# 1.net
KiCad netlist of a schematic drawn in EAGLE
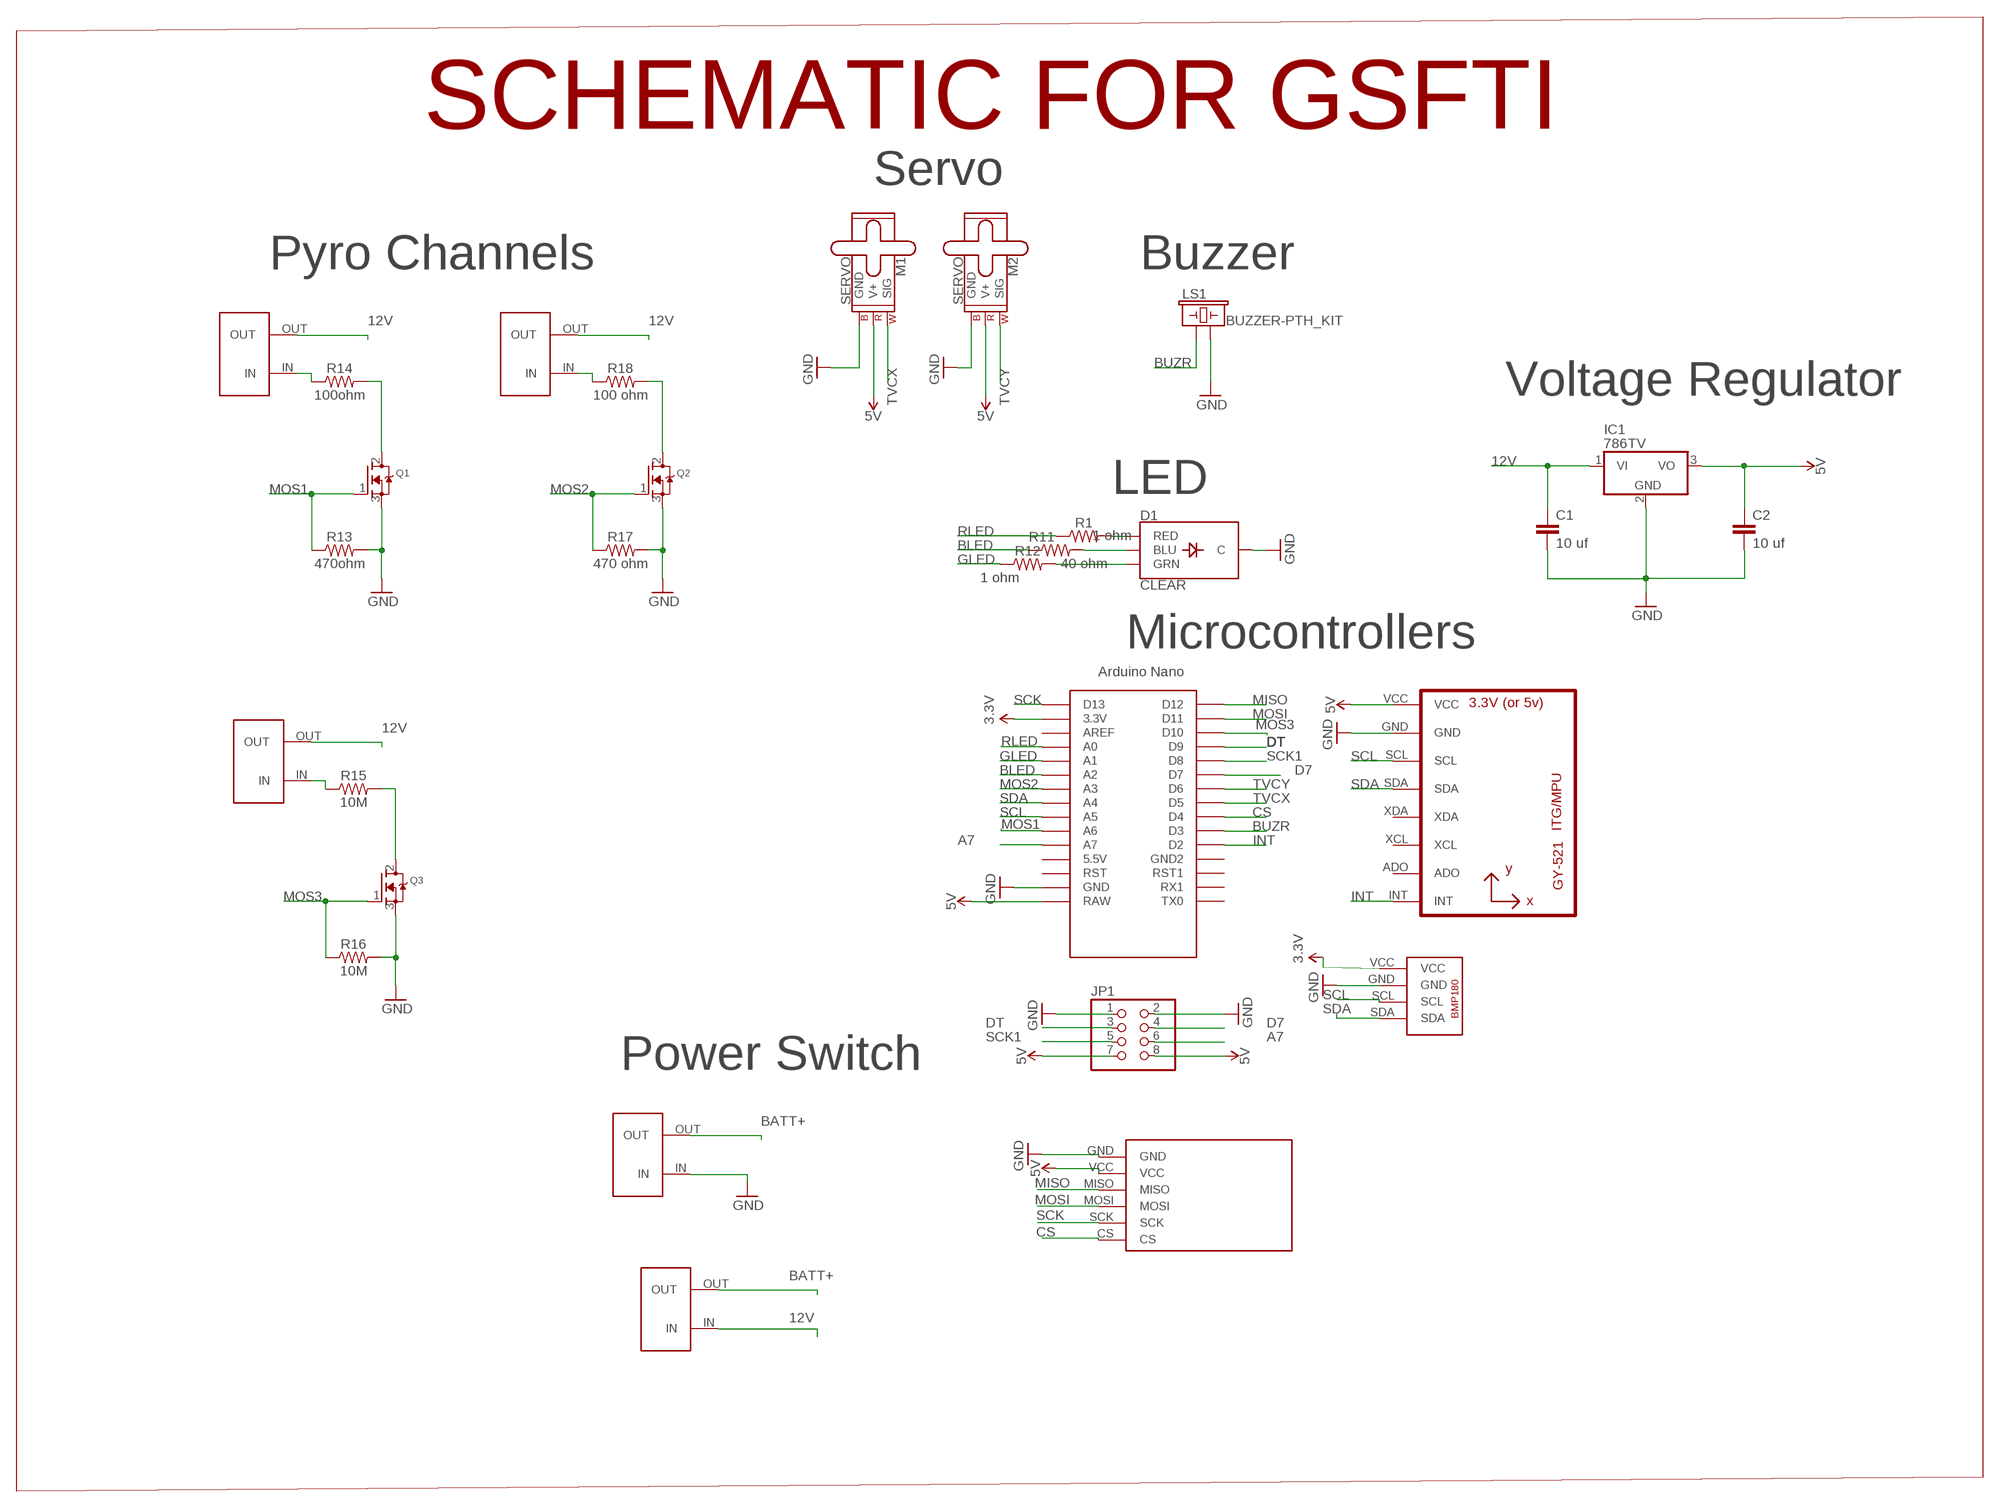
[diagram p0: schematic, sheet 1]

(export (version "E")
  (design (tool "Eeschema 10.0.6"))
  (components
    (comp (ref "C1")
      (value "10 uf")
      (footprint "eagle-import:C2.5-3")
      (libsource (lib "eagle-import") (part "C2,5-3"))
    )
    (comp (ref "C2")
      (value "10 uf")
      (footprint "eagle-import:C2.5-3")
      (libsource (lib "eagle-import") (part "C2,5-3"))
    )
    (comp (ref "D1")
      (value "CLEAR")
      (footprint "eagle-import:LED-RGB-THRU")
      (libsource (lib "eagle-import") (part "LED-RGB-CCCLEAR"))
    )
    (comp (ref "IC1")
      (value "786TV")
      (footprint "eagle-import:TO220V")
      (libsource (lib "eagle-import") (part "78TV6"))
    )
    (comp (ref "JP1")
      (value "PINHD-2X4")
      (footprint "eagle-import:2X04")
      (libsource (lib "eagle-import") (part "PINHD-2X4"))
    )
    (comp (ref "LS1")
      (value "BUZZER-PTH_KIT")
      (footprint "eagle-import:BUZZER-12MM-KIT")
      (libsource (lib "eagle-import") (part "BUZZER-PTH_KIT"))
    )
    (comp (ref "M1")
      (value "SERVO")
      (footprint "eagle-import:1X03")
      (libsource (lib "eagle-import") (part "SERVO"))
    )
    (comp (ref "M2")
      (value "SERVO")
      (footprint "eagle-import:1X03")
      (libsource (lib "eagle-import") (part "SERVO"))
    )
    (comp (ref "Q1")
      (value "MOSFET-NGDS_TO220V")
      (footprint "eagle-import:TO220V")
      (libsource (lib "eagle-import") (part "MOSFET-NGDS_TO220V"))
    )
    (comp (ref "Q2")
      (value "MOSFET-NGDS_TO220V")
      (footprint "eagle-import:TO220V")
      (libsource (lib "eagle-import") (part "MOSFET-NGDS_TO220V"))
    )
    (comp (ref "Q3")
      (value "MOSFET-NGDS_TO220V")
      (footprint "eagle-import:TO220V")
      (libsource (lib "eagle-import") (part "MOSFET-NGDS_TO220V"))
    )
    (comp (ref "R1")
      (value "1 ohm")
      (footprint "eagle-import:AXIAL-0.3")
      (libsource (lib "eagle-import") (part "10MOHM-HORIZ-1/4W-5%"))
    )
    (comp (ref "R11")
      (value "40 ohm")
      (footprint "eagle-import:AXIAL-0.3")
      (libsource (lib "eagle-import") (part "10MOHM-HORIZ-1/4W-5%"))
    )
    (comp (ref "R12")
      (value "1 ohm")
      (footprint "eagle-import:AXIAL-0.3")
      (libsource (lib "eagle-import") (part "10MOHM-HORIZ-1/4W-5%"))
    )
    (comp (ref "R13")
      (value "470ohm")
      (footprint "eagle-import:AXIAL-0.3")
      (libsource (lib "eagle-import") (part "10MOHM-HORIZ-1/4W-5%"))
    )
    (comp (ref "R14")
      (value "100ohm")
      (footprint "eagle-import:AXIAL-0.3")
      (libsource (lib "eagle-import") (part "10MOHM-HORIZ-1/4W-5%"))
    )
    (comp (ref "R15")
      (value "10M")
      (footprint "eagle-import:AXIAL-0.3")
      (libsource (lib "eagle-import") (part "10MOHM-HORIZ-1/4W-5%"))
    )
    (comp (ref "R16")
      (value "10M")
      (footprint "eagle-import:AXIAL-0.3")
      (libsource (lib "eagle-import") (part "10MOHM-HORIZ-1/4W-5%"))
    )
    (comp (ref "R17")
      (value "470 ohm")
      (footprint "eagle-import:AXIAL-0.3")
      (libsource (lib "eagle-import") (part "10MOHM-HORIZ-1/4W-5%"))
    )
    (comp (ref "R18")
      (value "100 ohm")
      (footprint "eagle-import:AXIAL-0.3")
      (libsource (lib "eagle-import") (part "10MOHM-HORIZ-1/4W-5%"))
    )
    (comp (ref "U$1")
      (value "NANO")
      (footprint "eagle-import:NANO")
      (libsource (lib "eagle-import") (part "NANO"))
    )
    (comp (ref "U$2")
      (value "BMP180")
      (footprint "eagle-import:BMP180")
      (libsource (lib "eagle-import") (part "BMP180"))
    )
    (comp (ref "U$3") (value "SD") (footprint "eagle-import:SD") (libsource (lib "eagle-import") (part "SD")))
    (comp (ref "U$4")
      (value "TERMINALBLOCKS")
      (footprint "eagle-import:TERMINALBLOCKS")
      (libsource (lib "eagle-import") (part "TERMINALBLOCKS_36144319_TERMINALBLOCKS"))
    )
    (comp (ref "U$7")
      (value "TERMINALBLOCKS")
      (footprint "eagle-import:TERMINALBLOCKS")
      (libsource (lib "eagle-import") (part "TERMINALBLOCKS"))
    )
    (comp (ref "U$8")
      (value "TERMINALBLOCKS")
      (footprint "eagle-import:TERMINALBLOCKS")
      (libsource (lib "eagle-import") (part "TERMINALBLOCKS"))
    )
    (comp (ref "U$9")
      (value "TERMINALBLOCKS")
      (footprint "eagle-import:TERMINALBLOCKS")
      (libsource (lib "eagle-import") (part "TERMINALBLOCKS"))
    )
    (comp (ref "U$10")
      (value "TERMINALBLOCKS")
      (footprint "eagle-import:TERMINALBLOCKS")
      (libsource (lib "eagle-import") (part "TERMINALBLOCKS"))
    )
    (comp (ref "U1")
      (value "GY-521MPU6050")
      (footprint "eagle-import:GY-521")
      (libsource (lib "eagle-import") (part "GY-521MPU6050"))
    )
  )
  (nets
    (net (code "1") (name "/12V") (class "Default")
      (node (ref "C1") (pin "1") (pinfunction "1_1") (pintype "passive"))
      (node (ref "IC1") (pin "1") (pinfunction "VI_1") (pintype "input"))
      (node (ref "U$10") (pin "OUT") (pinfunction "OUT_OUT") (pintype "bidirectional"))
      (node (ref "U$7") (pin "IN") (pinfunction "IN_IN") (pintype "bidirectional"))
      (node (ref "U$8") (pin "OUT") (pinfunction "OUT_OUT") (pintype "bidirectional"))
      (node (ref "U$9") (pin "OUT") (pinfunction "OUT_OUT") (pintype "bidirectional"))
    )
    (net (code "2") (name "/A7") (class "Default")
      (node (ref "JP1") (pin "6") (pinfunction "6_6") (pintype "passive"))
      (node (ref "U$1") (pin "A7") (pinfunction "A7_A7") (pintype "bidirectional"))
    )
    (net (code "3") (name "/BATT+") (class "Default")
      (node (ref "U$4") (pin "OUT") (pinfunction "OUT_OUT") (pintype "bidirectional"))
      (node (ref "U$7") (pin "OUT") (pinfunction "OUT_OUT") (pintype "bidirectional"))
    )
    (net (code "4") (name "/BLED") (class "Default")
      (node (ref "R11") (pin "P$1") (pinfunction "1_P$1") (pintype "passive"))
      (node (ref "U$1") (pin "A2") (pinfunction "A2_A2") (pintype "bidirectional"))
    )
    (net (code "5") (name "/BUZR") (class "Default")
      (node (ref "LS1") (pin "+") (pinfunction "1_+") (pintype "passive"))
      (node (ref "U$1") (pin "D3") (pinfunction "D3_D3") (pintype "bidirectional"))
    )
    (net (code "6") (name "/CS") (class "Default")
      (node (ref "U$1") (pin "D4") (pinfunction "D4_D4") (pintype "bidirectional"))
      (node (ref "U$3") (pin "CS") (pinfunction "CS_CS") (pintype "bidirectional"))
    )
    (net (code "7") (name "/D7") (class "Default")
      (node (ref "JP1") (pin "4") (pinfunction "4_4") (pintype "passive"))
      (node (ref "U$1") (pin "D7") (pinfunction "D7_D7") (pintype "bidirectional"))
    )
    (net (code "8") (name "/DT") (class "Default")
      (node (ref "JP1") (pin "3") (pinfunction "3_3") (pintype "passive"))
      (node (ref "U$1") (pin "D9") (pinfunction "D9_D9") (pintype "bidirectional"))
    )
    (net (code "9") (name "/GLED") (class "Default")
      (node (ref "R12") (pin "P$1") (pinfunction "1_P$1") (pintype "passive"))
      (node (ref "U$1") (pin "A1") (pinfunction "A1_A1") (pintype "bidirectional"))
    )
    (net (code "10") (name "/INT") (class "Default")
      (node (ref "U$1") (pin "D2") (pinfunction "D2_D2") (pintype "bidirectional"))
      (node (ref "U1") (pin "INT") (pinfunction "INT_INT") (pintype "bidirectional"))
    )
    (net (code "11") (name "/MISO") (class "Default")
      (node (ref "U$1") (pin "D12") (pinfunction "D12_D12") (pintype "bidirectional"))
      (node (ref "U$3") (pin "MISO") (pinfunction "MISO_MISO") (pintype "bidirectional"))
    )
    (net (code "12") (name "/MOS1") (class "Default")
      (node (ref "Q1") (pin "1") (pinfunction "G_1") (pintype "bidirectional"))
      (node (ref "R13") (pin "P$1") (pinfunction "1_P$1") (pintype "passive"))
      (node (ref "U$1") (pin "A6") (pinfunction "A6_A6") (pintype "bidirectional"))
    )
    (net (code "13") (name "/MOS2") (class "Default")
      (node (ref "Q2") (pin "1") (pinfunction "G_1") (pintype "bidirectional"))
      (node (ref "R17") (pin "P$1") (pinfunction "1_P$1") (pintype "passive"))
      (node (ref "U$1") (pin "A3") (pinfunction "A3_A3") (pintype "bidirectional"))
    )
    (net (code "14") (name "/MOS3") (class "Default")
      (node (ref "Q3") (pin "1") (pinfunction "G_1") (pintype "bidirectional"))
      (node (ref "R16") (pin "P$1") (pinfunction "1_P$1") (pintype "passive"))
      (node (ref "U$1") (pin "D10") (pinfunction "D10_D10") (pintype "bidirectional"))
    )
    (net (code "15") (name "/MOSI") (class "Default")
      (node (ref "U$1") (pin "D11") (pinfunction "D11_D11") (pintype "bidirectional"))
      (node (ref "U$3") (pin "MOSI") (pinfunction "MOSI_MOSI") (pintype "bidirectional"))
    )
    (net (code "16") (name "/RLED") (class "Default")
      (node (ref "R1") (pin "P$1") (pinfunction "1_P$1") (pintype "passive"))
      (node (ref "U$1") (pin "A0") (pinfunction "A0_A0") (pintype "bidirectional"))
    )
    (net (code "17") (name "/SCK") (class "Default")
      (node (ref "U$1") (pin "D13") (pinfunction "D13_D13") (pintype "bidirectional"))
      (node (ref "U$3") (pin "SCK") (pinfunction "SCK_SCK") (pintype "bidirectional"))
    )
    (net (code "18") (name "/SCK1") (class "Default")
      (node (ref "JP1") (pin "5") (pinfunction "5_5") (pintype "passive"))
      (node (ref "U$1") (pin "D8") (pinfunction "D8_D8") (pintype "bidirectional"))
    )
    (net (code "19") (name "/SCL") (class "Default")
      (node (ref "U$1") (pin "A5") (pinfunction "A5_A5") (pintype "bidirectional"))
      (node (ref "U$2") (pin "SCL") (pinfunction "SCL_SCL") (pintype "bidirectional"))
      (node (ref "U1") (pin "SCL") (pinfunction "SCL_SCL") (pintype "bidirectional"))
    )
    (net (code "20") (name "/SDA") (class "Default")
      (node (ref "U$1") (pin "A4") (pinfunction "A4_A4") (pintype "bidirectional"))
      (node (ref "U$2") (pin "SDA") (pinfunction "SDA_SDA") (pintype "bidirectional"))
      (node (ref "U1") (pin "SDA") (pinfunction "SDA_SDA") (pintype "bidirectional"))
    )
    (net (code "21") (name "/TVCX") (class "Default")
      (node (ref "M1") (pin "1") (pinfunction "SIG_1") (pintype "bidirectional"))
      (node (ref "U$1") (pin "D5") (pinfunction "D5_D5") (pintype "bidirectional"))
    )
    (net (code "22") (name "/TVCY") (class "Default")
      (node (ref "M2") (pin "1") (pinfunction "SIG_1") (pintype "bidirectional"))
      (node (ref "U$1") (pin "D6") (pinfunction "D6_D6") (pintype "bidirectional"))
    )
    (net (code "23") (name "3.3V") (class "Default")
      (node (ref "U$1") (pin "3.3V") (pinfunction "3.3V_3.3V") (pintype "bidirectional"))
      (node (ref "U$2") (pin "VCC") (pinfunction "VCC_VCC") (pintype "bidirectional"))
    )
    (net (code "24") (name "5V") (class "Default")
      (node (ref "C2") (pin "1") (pinfunction "1_1") (pintype "passive"))
      (node (ref "IC1") (pin "3") (pinfunction "VO_3") (pintype "passive"))
      (node (ref "JP1") (pin "7") (pinfunction "7_7") (pintype "passive"))
      (node (ref "JP1") (pin "8") (pinfunction "8_8") (pintype "passive"))
      (node (ref "M1") (pin "2") (pinfunction "V+_2") (pintype "bidirectional"))
      (node (ref "M2") (pin "2") (pinfunction "V+_2") (pintype "bidirectional"))
      (node (ref "U$1") (pin "RAW") (pinfunction "RAW_RAW") (pintype "bidirectional"))
      (node (ref "U$3") (pin "VCC") (pinfunction "VCC_VCC") (pintype "bidirectional"))
      (node (ref "U1") (pin "VCC") (pinfunction "VCC_VCC") (pintype "bidirectional"))
    )
    (net (code "25") (name "GND") (class "Default")
      (node (ref "C1") (pin "2") (pinfunction "2_2") (pintype "passive"))
      (node (ref "C2") (pin "2") (pinfunction "2_2") (pintype "passive"))
      (node (ref "D1") (pin "2") (pinfunction "C_2") (pintype "bidirectional"))
      (node (ref "IC1") (pin "2") (pinfunction "GND_2") (pintype "passive"))
      (node (ref "JP1") (pin "1") (pinfunction "1_1") (pintype "passive"))
      (node (ref "JP1") (pin "2") (pinfunction "2_2") (pintype "passive"))
      (node (ref "LS1") (pin "-") (pinfunction "2_-") (pintype "passive"))
      (node (ref "M1") (pin "3") (pinfunction "GND_3") (pintype "bidirectional"))
      (node (ref "M2") (pin "3") (pinfunction "GND_3") (pintype "bidirectional"))
      (node (ref "Q1") (pin "3") (pinfunction "S_3") (pintype "bidirectional"))
      (node (ref "Q2") (pin "3") (pinfunction "S_3") (pintype "bidirectional"))
      (node (ref "Q3") (pin "3") (pinfunction "S_3") (pintype "bidirectional"))
      (node (ref "R13") (pin "P$2") (pinfunction "2_P$2") (pintype "passive"))
      (node (ref "R16") (pin "P$2") (pinfunction "2_P$2") (pintype "passive"))
      (node (ref "R17") (pin "P$2") (pinfunction "2_P$2") (pintype "passive"))
      (node (ref "U$1") (pin "GND") (pinfunction "GND_GND") (pintype "bidirectional"))
      (node (ref "U$2") (pin "GND") (pinfunction "GND_GND") (pintype "bidirectional"))
      (node (ref "U$3") (pin "GND") (pinfunction "GND_GND") (pintype "bidirectional"))
      (node (ref "U$4") (pin "IN") (pinfunction "IN_IN") (pintype "bidirectional"))
      (node (ref "U1") (pin "GND") (pinfunction "GND_GND") (pintype "bidirectional"))
    )
    (net (code "26") (name "Net-(D1-BLU)") (class "Default")
      (node (ref "D1") (pin "4") (pinfunction "BLU_4") (pintype "bidirectional"))
      (node (ref "R11") (pin "P$2") (pinfunction "2_P$2") (pintype "passive"))
    )
    (net (code "27") (name "Net-(D1-GRN)") (class "Default")
      (node (ref "D1") (pin "3") (pinfunction "GRN_3") (pintype "bidirectional"))
      (node (ref "R12") (pin "P$2") (pinfunction "2_P$2") (pintype "passive"))
    )
    (net (code "28") (name "Net-(D1-RED)") (class "Default")
      (node (ref "D1") (pin "1") (pinfunction "RED_1") (pintype "bidirectional"))
      (node (ref "R1") (pin "P$2") (pinfunction "2_P$2") (pintype "passive"))
    )
    (net (code "29") (name "Net-(Q1-D)") (class "Default")
      (node (ref "Q1") (pin "2") (pinfunction "D_2") (pintype "bidirectional"))
      (node (ref "R14") (pin "P$2") (pinfunction "2_P$2") (pintype "passive"))
    )
    (net (code "30") (name "Net-(Q2-D)") (class "Default")
      (node (ref "Q2") (pin "2") (pinfunction "D_2") (pintype "bidirectional"))
      (node (ref "R18") (pin "P$2") (pinfunction "2_P$2") (pintype "passive"))
    )
    (net (code "31") (name "Net-(Q3-D)") (class "Default")
      (node (ref "Q3") (pin "2") (pinfunction "D_2") (pintype "bidirectional"))
      (node (ref "R15") (pin "P$2") (pinfunction "2_P$2") (pintype "passive"))
    )
    (net (code "32") (name "Net-(R14-1)") (class "Default")
      (node (ref "R14") (pin "P$1") (pinfunction "1_P$1") (pintype "passive"))
      (node (ref "U$8") (pin "IN") (pinfunction "IN_IN") (pintype "bidirectional"))
    )
    (net (code "33") (name "Net-(R15-1)") (class "Default")
      (node (ref "R15") (pin "P$1") (pinfunction "1_P$1") (pintype "passive"))
      (node (ref "U$10") (pin "IN") (pinfunction "IN_IN") (pintype "bidirectional"))
    )
    (net (code "34") (name "Net-(R18-1)") (class "Default")
      (node (ref "R18") (pin "P$1") (pinfunction "1_P$1") (pintype "passive"))
      (node (ref "U$9") (pin "IN") (pinfunction "IN_IN") (pintype "bidirectional"))
    )
    (net (code "35") (name "unconnected-(U$1-5.5V-Pad5V)") (class "Default")
      (node (ref "U$1") (pin "5V") (pinfunction "5.5V_5V") (pintype "bidirectional"))
    )
    (net (code "36") (name "unconnected-(U$1-GND2-PadGND1)") (class "Default")
      (node (ref "U$1") (pin "GND1") (pinfunction "GND2_GND1") (pintype "bidirectional"))
    )
    (net (code "37") (name "unconnected-(U$1-PadAREF)") (class "Default")
      (node (ref "U$1") (pin "AREF") (pinfunction "AREF_AREF") (pintype "bidirectional"))
    )
    (net (code "38") (name "unconnected-(U$1-PadICSP1)") (class "Default")
      (node (ref "U$1") (pin "ICSP1") (pinfunction "ICSP1_ICSP1") (pintype "bidirectional"))
    )
    (net (code "39") (name "unconnected-(U$1-PadICSP2)") (class "Default")
      (node (ref "U$1") (pin "ICSP2") (pinfunction "ICSP2_ICSP2") (pintype "bidirectional"))
    )
    (net (code "40") (name "unconnected-(U$1-PadICSP3)") (class "Default")
      (node (ref "U$1") (pin "ICSP3") (pinfunction "ICSP3_ICSP3") (pintype "bidirectional"))
    )
    (net (code "41") (name "unconnected-(U$1-PadICSP4)") (class "Default")
      (node (ref "U$1") (pin "ICSP4") (pinfunction "ICSP4_ICSP4") (pintype "bidirectional"))
    )
    (net (code "42") (name "unconnected-(U$1-PadICSP5)") (class "Default")
      (node (ref "U$1") (pin "ICSP5") (pinfunction "ICSP5_ICSP5") (pintype "bidirectional"))
    )
    (net (code "43") (name "unconnected-(U$1-PadICSP6)") (class "Default")
      (node (ref "U$1") (pin "ICSP6") (pinfunction "ICSP6_ICSP6") (pintype "bidirectional"))
    )
    (net (code "44") (name "unconnected-(U$1-PadRST)") (class "Default")
      (node (ref "U$1") (pin "RST") (pinfunction "RST_RST") (pintype "bidirectional"))
    )
    (net (code "45") (name "unconnected-(U$1-PadRST1)") (class "Default")
      (node (ref "U$1") (pin "RST1") (pinfunction "RST1_RST1") (pintype "bidirectional"))
    )
    (net (code "46") (name "unconnected-(U$1-PadRX1)") (class "Default")
      (node (ref "U$1") (pin "RX1") (pinfunction "RX1_RX1") (pintype "bidirectional"))
    )
    (net (code "47") (name "unconnected-(U$1-PadTX0)") (class "Default")
      (node (ref "U$1") (pin "TX0") (pinfunction "TX0_TX0") (pintype "bidirectional"))
    )
    (net (code "48") (name "unconnected-(U1-PadADO)") (class "Default")
      (node (ref "U1") (pin "ADO") (pinfunction "ADO_ADO") (pintype "bidirectional"))
    )
    (net (code "49") (name "unconnected-(U1-PadXCL)") (class "Default")
      (node (ref "U1") (pin "XCL") (pinfunction "XCL_XCL") (pintype "bidirectional"))
    )
    (net (code "50") (name "unconnected-(U1-PadXDA)") (class "Default")
      (node (ref "U1") (pin "XDA") (pinfunction "XDA_XDA") (pintype "bidirectional"))
    )
  )
)
